# URC-LCD.net
KiCad netlist of a schematic drawn in EAGLE
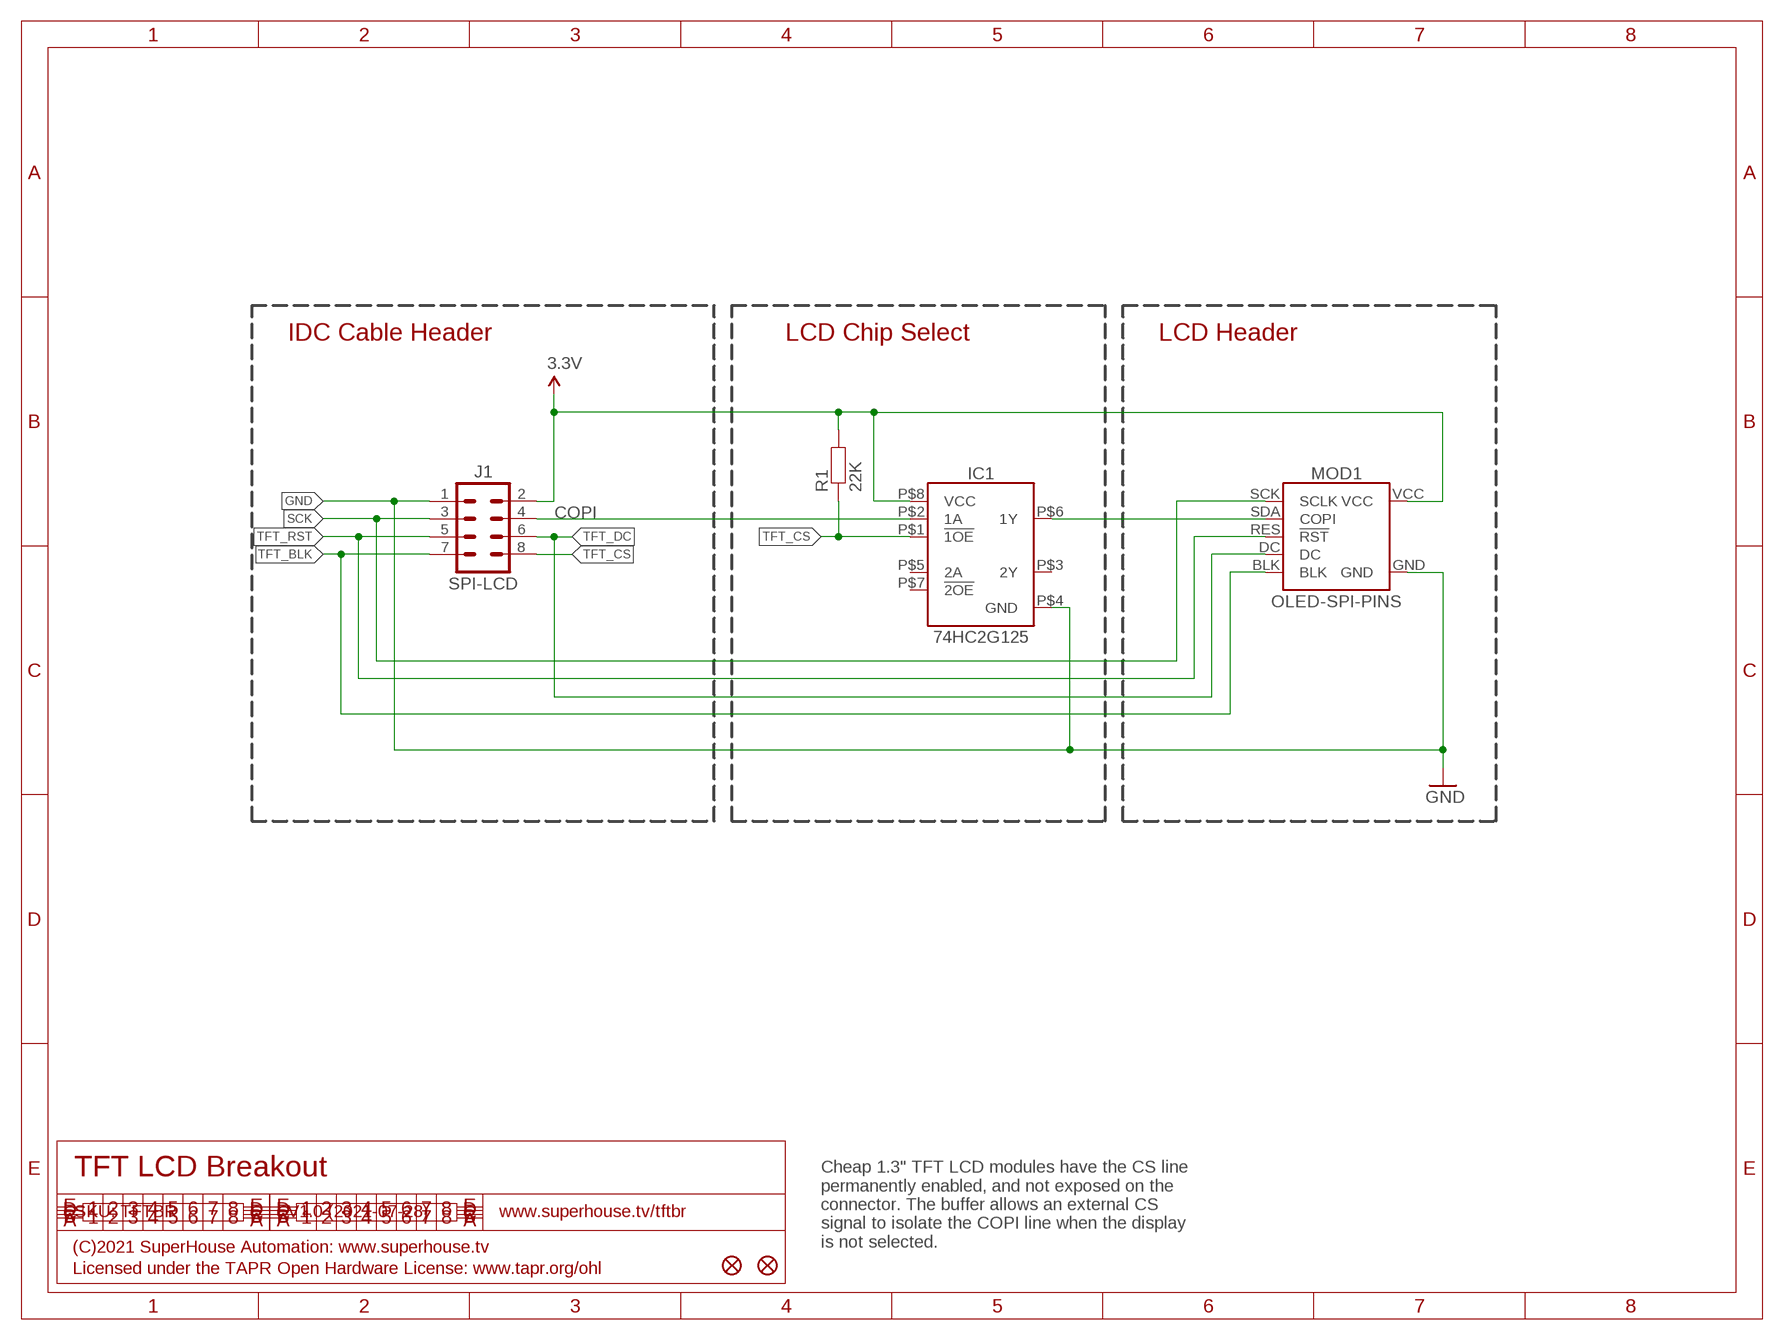
[diagram p0: schematic, sheet 1]

(export (version "E")
  (design (tool "Eeschema 10.0.6"))
  (components
    (comp (ref "FID1")
      (value "FIDUCIAL1X2.5")
      (footprint "eagle-import:FIDUCIAL-1X2.5")
      (libsource (lib "eagle-import") (part "FIDUCIAL1X2.5"))
    )
    (comp (ref "FID3")
      (value "FIDUCIAL1X2.5")
      (footprint "eagle-import:FIDUCIAL-1X2.5")
      (libsource (lib "eagle-import") (part "FIDUCIAL1X2.5"))
    )
    (comp (ref "IC1")
      (value "74HC2G125")
      (footprint "eagle-import:74HC2G125")
      (libsource (lib "eagle-import") (part "74HC2G125-TSSOP8"))
    )
    (comp (ref "J1")
      (value "SPI-LCD")
      (footprint "eagle-import:2X04-2.54-SHROUDED")
      (libsource (lib "eagle-import") (part "M02X4-SHROUD"))
    )
    (comp (ref "MOD1")
      (value "OLED-SPI-PINS")
      (footprint "eagle-import:OLED-240X240-1.3")
      (libsource (lib "eagle-import") (part "OLED-SPI-PINS"))
    )
    (comp (ref "R1")
      (value "22K")
      (footprint "eagle-import:R0603")
      (libsource (lib "eagle-import") (part "RESISTOR0603"))
    )
  )
  (nets
    (net (code "1") (name "/COPI") (class "Default")
      (node (ref "IC1") (pin "P$2") (pinfunction "1A_P$2") (pintype "bidirectional"))
      (node (ref "J1") (pin "4") (pinfunction "4_4") (pintype "passive"))
    )
    (net (code "2") (name "3.3V") (class "Default")
      (node (ref "IC1") (pin "P$8") (pinfunction "VCC_P$8") (pintype "bidirectional"))
      (node (ref "J1") (pin "2") (pinfunction "2_2") (pintype "passive"))
      (node (ref "MOD1") (pin "VCC") (pinfunction "VCC_VCC") (pintype "bidirectional"))
      (node (ref "R1") (pin "2") (pinfunction "2_2") (pintype "passive"))
    )
    (net (code "3") (name "GND") (class "Default")
      (node (ref "IC1") (pin "P$4") (pinfunction "GND_P$4") (pintype "bidirectional"))
      (node (ref "J1") (pin "1") (pinfunction "1_1") (pintype "passive"))
      (node (ref "MOD1") (pin "GND") (pinfunction "GND_GND") (pintype "bidirectional"))
    )
    (net (code "4") (name "Net-(IC1-1Y)") (class "Default")
      (node (ref "IC1") (pin "P$6") (pinfunction "1Y_P$6") (pintype "bidirectional"))
      (node (ref "MOD1") (pin "SDA") (pinfunction "COPI_SDA") (pintype "bidirectional"))
    )
    (net (code "5") (name "SCK") (class "Default")
      (node (ref "J1") (pin "3") (pinfunction "3_3") (pintype "passive"))
      (node (ref "MOD1") (pin "SCK") (pinfunction "SCLK_SCK") (pintype "bidirectional"))
    )
    (net (code "6") (name "TFT_BLK") (class "Default")
      (node (ref "J1") (pin "7") (pinfunction "7_7") (pintype "passive"))
      (node (ref "MOD1") (pin "BLK") (pinfunction "BLK_BLK") (pintype "bidirectional"))
    )
    (net (code "7") (name "TFT_CS") (class "Default")
      (node (ref "IC1") (pin "P$1") (pinfunction "~{1OE}_P$1") (pintype "bidirectional"))
      (node (ref "J1") (pin "8") (pinfunction "8_8") (pintype "passive"))
      (node (ref "R1") (pin "1") (pinfunction "1_1") (pintype "passive"))
    )
    (net (code "8") (name "TFT_DC") (class "Default")
      (node (ref "J1") (pin "6") (pinfunction "6_6") (pintype "passive"))
      (node (ref "MOD1") (pin "DC") (pinfunction "DC_DC") (pintype "bidirectional"))
    )
    (net (code "9") (name "TFT_RST") (class "Default")
      (node (ref "J1") (pin "5") (pinfunction "5_5") (pintype "passive"))
      (node (ref "MOD1") (pin "RES") (pinfunction "~{RST}_RES") (pintype "bidirectional"))
    )
    (net (code "10") (name "unconnected-(IC1-2A-PadP$5)") (class "Default")
      (node (ref "IC1") (pin "P$5") (pinfunction "2A_P$5") (pintype "bidirectional"))
    )
    (net (code "11") (name "unconnected-(IC1-2Y-PadP$3)") (class "Default")
      (node (ref "IC1") (pin "P$3") (pinfunction "2Y_P$3") (pintype "bidirectional"))
    )
    (net (code "12") (name "unconnected-(IC1-~{2OE}-PadP$7)") (class "Default")
      (node (ref "IC1") (pin "P$7") (pinfunction "~{2OE}_P$7") (pintype "bidirectional"))
    )
  )
)
